# Rapide64a.net
KiCad netlist of a schematic drawn in EAGLE
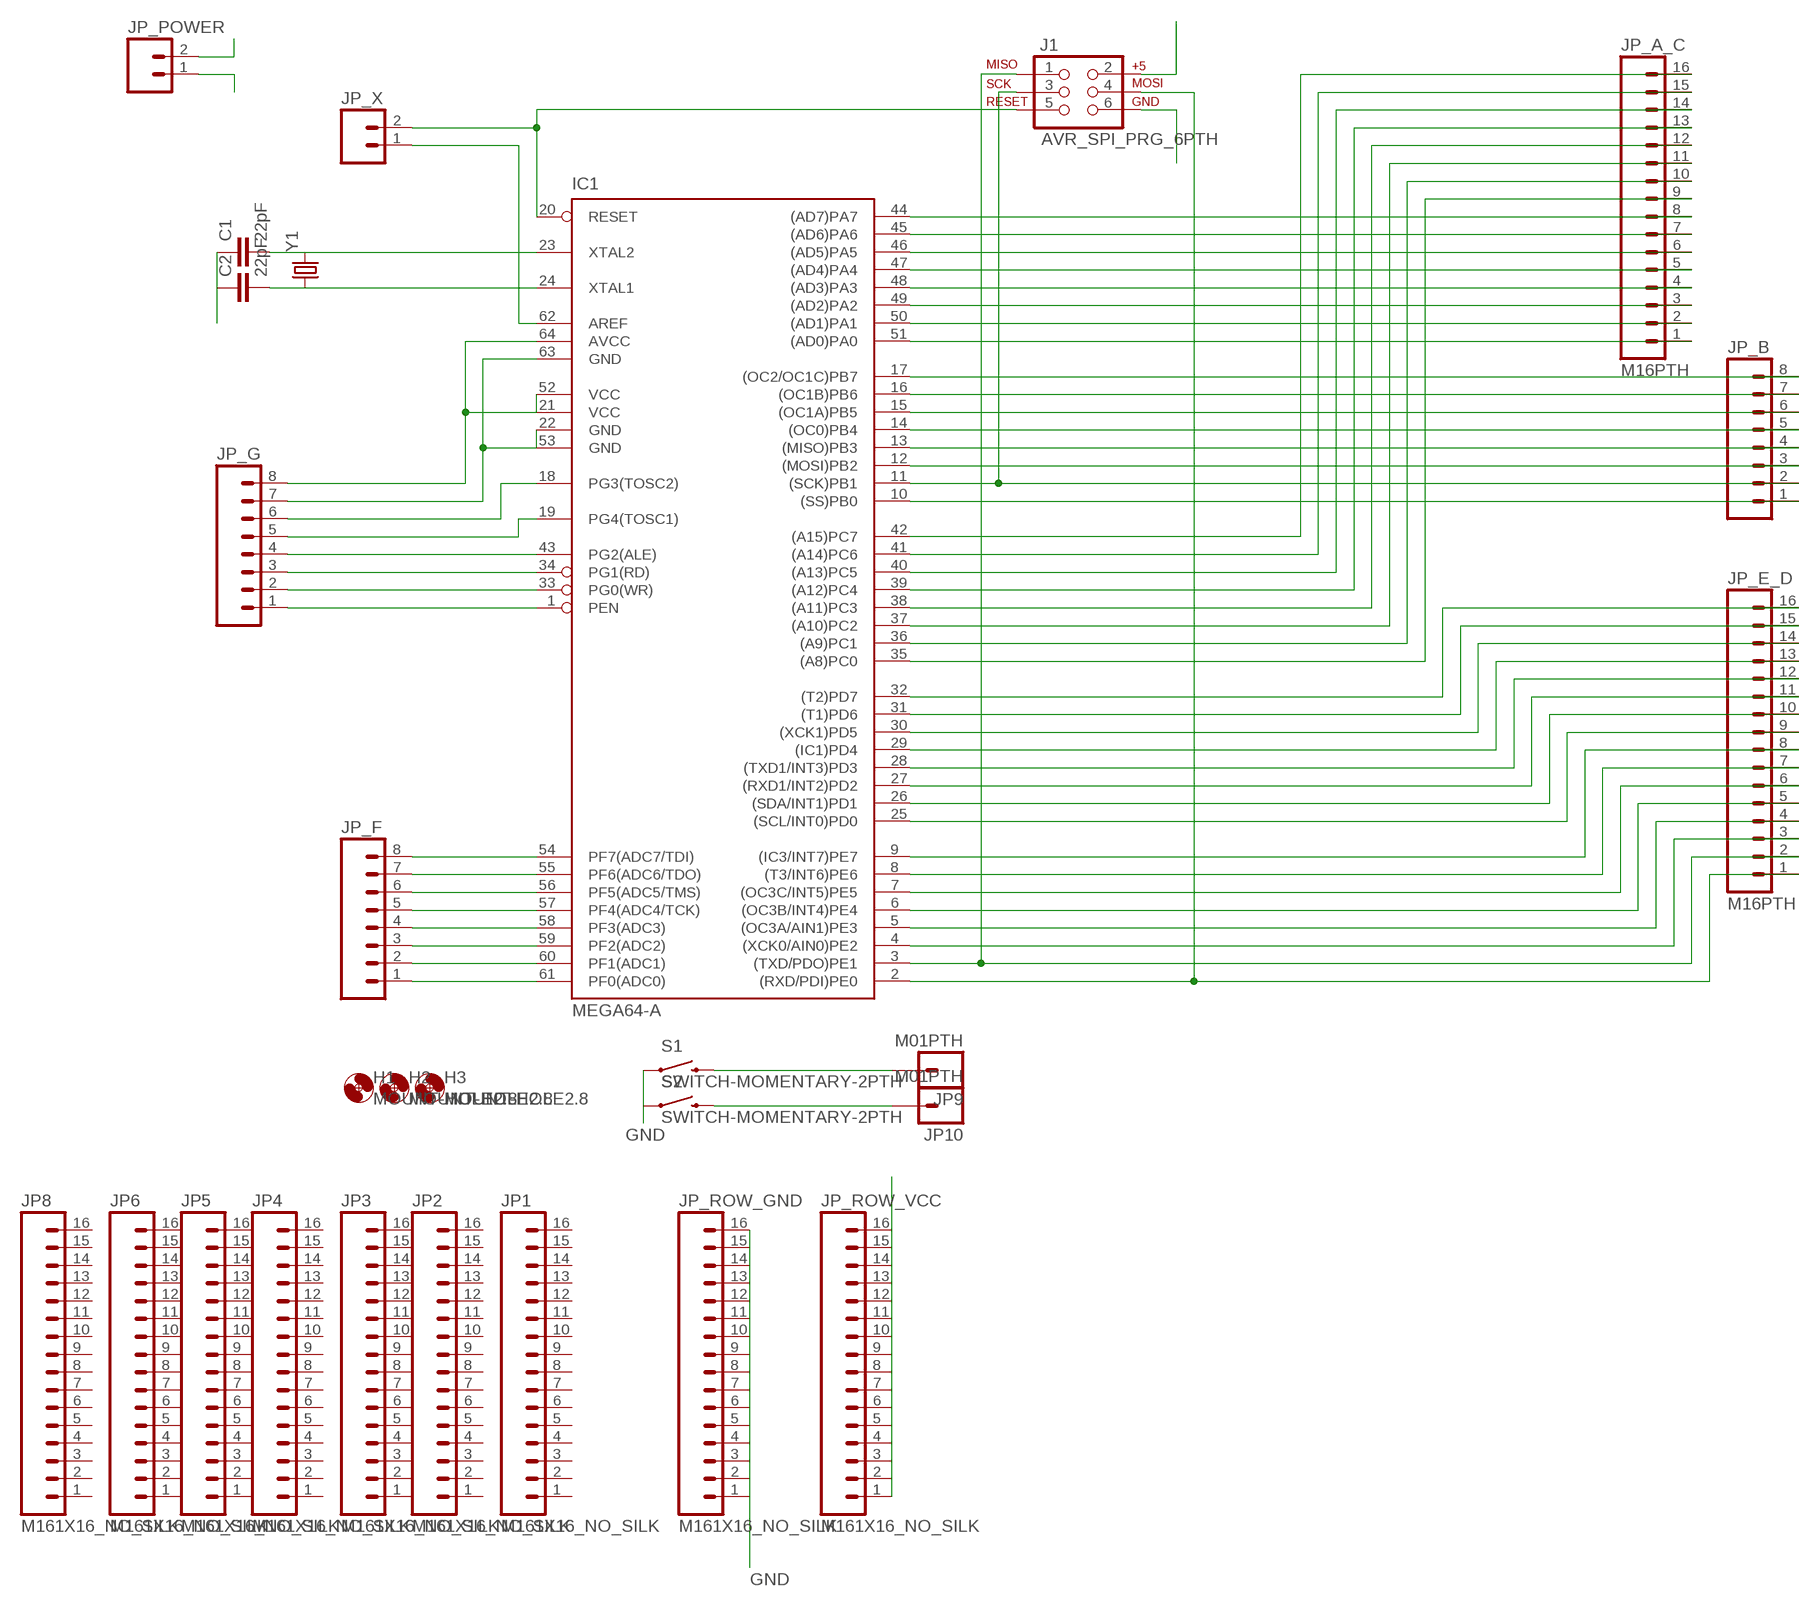
[diagram p0: schematic, sheet 1]

(export (version "E")
  (design (tool "Eeschema 10.0.6"))
  (components
    (comp (ref "C1")
      (value "22pF")
      (footprint "eagle-import:C025-024X044")
      (libsource (lib "eagle-import") (part "C-EU025-024X044"))
    )
    (comp (ref "C2")
      (value "22pF")
      (footprint "eagle-import:C025-024X044")
      (libsource (lib "eagle-import") (part "C-EU025-024X044"))
    )
    (comp (ref "H1")
      (value "MOUNT-HOLE2.8")
      (footprint "eagle-import:2,8")
      (libsource (lib "eagle-import") (part "MOUNT-HOLE2.8"))
    )
    (comp (ref "H2")
      (value "MOUNT-HOLE2.8")
      (footprint "eagle-import:2,8")
      (libsource (lib "eagle-import") (part "MOUNT-HOLE2.8"))
    )
    (comp (ref "H3")
      (value "MOUNT-HOLE2.8")
      (footprint "eagle-import:2,8")
      (libsource (lib "eagle-import") (part "MOUNT-HOLE2.8"))
    )
    (comp (ref "IC1")
      (value "MEGA64-A")
      (footprint "eagle-import:TQFP64")
      (fields (field (name "MPN") "ATMEGA64-16AU"))
      (libsource (lib "eagle-import") (part "MEGA64-A"))
    )
    (comp (ref "J1")
      (value "AVR_SPI_PRG_6PTH")
      (footprint "eagle-import:2X3")
      (libsource (lib "eagle-import") (part "AVR_SPI_PRG_6PTH"))
    )
    (comp (ref "JP1")
      (value "M161X16_NO_SILK")
      (footprint "eagle-import:1X16_NO_SILK")
      (libsource (lib "eagle-import") (part "M161X16_NO_SILK"))
    )
    (comp (ref "JP2")
      (value "M161X16_NO_SILK")
      (footprint "eagle-import:1X16_NO_SILK")
      (libsource (lib "eagle-import") (part "M161X16_NO_SILK"))
    )
    (comp (ref "JP3")
      (value "M161X16_NO_SILK")
      (footprint "eagle-import:1X16_NO_SILK")
      (libsource (lib "eagle-import") (part "M161X16_NO_SILK"))
    )
    (comp (ref "JP4")
      (value "M161X16_NO_SILK")
      (footprint "eagle-import:1X16_NO_SILK")
      (libsource (lib "eagle-import") (part "M161X16_NO_SILK"))
    )
    (comp (ref "JP5")
      (value "M161X16_NO_SILK")
      (footprint "eagle-import:1X16_NO_SILK")
      (libsource (lib "eagle-import") (part "M161X16_NO_SILK"))
    )
    (comp (ref "JP6")
      (value "M161X16_NO_SILK")
      (footprint "eagle-import:1X16_NO_SILK")
      (libsource (lib "eagle-import") (part "M161X16_NO_SILK"))
    )
    (comp (ref "JP8")
      (value "M161X16_NO_SILK")
      (footprint "eagle-import:1X16_NO_SILK")
      (libsource (lib "eagle-import") (part "M161X16_NO_SILK"))
    )
    (comp (ref "JP9")
      (value "M01PTH")
      (footprint "eagle-import:1X01")
      (libsource (lib "eagle-import") (part "M01PTH"))
    )
    (comp (ref "JP10")
      (value "M01PTH")
      (footprint "eagle-import:1X01")
      (libsource (lib "eagle-import") (part "M01PTH"))
    )
    (comp (ref "JP_A_C")
      (value "M16PTH")
      (footprint "eagle-import:1X16")
      (libsource (lib "eagle-import") (part "M16PTH"))
    )
    (comp (ref "JP_B")
      (value "M081X08")
      (footprint "eagle-import:1X08")
      (libsource (lib "eagle-import") (part "M081X08"))
    )
    (comp (ref "JP_E_D")
      (value "M16PTH")
      (footprint "eagle-import:1X16")
      (libsource (lib "eagle-import") (part "M16PTH"))
    )
    (comp (ref "JP_F")
      (value "M081X08")
      (footprint "eagle-import:1X08")
      (libsource (lib "eagle-import") (part "M081X08"))
    )
    (comp (ref "JP_G")
      (value "M081X08")
      (footprint "eagle-import:1X08")
      (libsource (lib "eagle-import") (part "M081X08"))
    )
    (comp (ref "JP_POWER")
      (value "M02PTH")
      (footprint "eagle-import:1X02")
      (libsource (lib "eagle-import") (part "M02PTH"))
    )
    (comp (ref "JP_ROW_GND")
      (value "M161X16_NO_SILK")
      (footprint "eagle-import:1X16_NO_SILK")
      (libsource (lib "eagle-import") (part "M161X16_NO_SILK"))
    )
    (comp (ref "JP_ROW_VCC")
      (value "M161X16_NO_SILK")
      (footprint "eagle-import:1X16_NO_SILK")
      (libsource (lib "eagle-import") (part "M161X16_NO_SILK"))
    )
    (comp (ref "JP_X")
      (value "M02PTH")
      (footprint "eagle-import:1X02")
      (libsource (lib "eagle-import") (part "M02PTH"))
    )
    (comp (ref "S1")
      (value "SWITCH-MOMENTARY-2PTH")
      (footprint "eagle-import:TACTILE-PTH")
      (libsource (lib "eagle-import") (part "SWITCH-MOMENTARY-2PTH"))
    )
    (comp (ref "S2")
      (value "SWITCH-MOMENTARY-2PTH")
      (footprint "eagle-import:TACTILE-PTH")
      (libsource (lib "eagle-import") (part "SWITCH-MOMENTARY-2PTH"))
    )
    (comp (ref "Y1")
      (value "CRYSTALHC49UV")
      (footprint "eagle-import:HC49U-V")
      (libsource (lib "eagle-import") (part "CRYSTALHC49UV"))
    )
  )
  (nets
    (net (code "1") (name "/GND") (class "Default")
      (node (ref "C1") (pin "1") (pinfunction "1_1") (pintype "passive"))
      (node (ref "C2") (pin "1") (pinfunction "1_1") (pintype "passive"))
      (node (ref "IC1") (pin "22") (pinfunction "GND_22") (pintype "power_in"))
      (node (ref "IC1") (pin "53") (pinfunction "GND_53") (pintype "power_in"))
      (node (ref "IC1") (pin "63") (pinfunction "GND_63") (pintype "power_in"))
      (node (ref "J1") (pin "6") (pinfunction "6_6") (pintype "passive"))
      (node (ref "JP_G") (pin "7") (pinfunction "7_7") (pintype "passive"))
      (node (ref "JP_POWER") (pin "1") (pinfunction "1_1") (pintype "passive"))
      (node (ref "JP_ROW_GND") (pin "1") (pinfunction "1_1") (pintype "passive"))
      (node (ref "JP_ROW_GND") (pin "10") (pinfunction "10_10") (pintype "passive"))
      (node (ref "JP_ROW_GND") (pin "11") (pinfunction "11_11") (pintype "passive"))
      (node (ref "JP_ROW_GND") (pin "12") (pinfunction "12_12") (pintype "passive"))
      (node (ref "JP_ROW_GND") (pin "13") (pinfunction "13_13") (pintype "passive"))
      (node (ref "JP_ROW_GND") (pin "14") (pinfunction "14_14") (pintype "passive"))
      (node (ref "JP_ROW_GND") (pin "15") (pinfunction "15_15") (pintype "passive"))
      (node (ref "JP_ROW_GND") (pin "16") (pinfunction "16_16") (pintype "passive"))
      (node (ref "JP_ROW_GND") (pin "2") (pinfunction "2_2") (pintype "passive"))
      (node (ref "JP_ROW_GND") (pin "3") (pinfunction "3_3") (pintype "passive"))
      (node (ref "JP_ROW_GND") (pin "4") (pinfunction "4_4") (pintype "passive"))
      (node (ref "JP_ROW_GND") (pin "5") (pinfunction "5_5") (pintype "passive"))
      (node (ref "JP_ROW_GND") (pin "6") (pinfunction "6_6") (pintype "passive"))
      (node (ref "JP_ROW_GND") (pin "7") (pinfunction "7_7") (pintype "passive"))
      (node (ref "JP_ROW_GND") (pin "8") (pinfunction "8_8") (pintype "passive"))
      (node (ref "JP_ROW_GND") (pin "9") (pinfunction "9_9") (pintype "passive"))
      (node (ref "S1") (pin "1") (pinfunction "1_1") (pintype "passive"))
      (node (ref "S2") (pin "1") (pinfunction "1_1") (pintype "passive"))
    )
    (net (code "2") (name "/VCC") (class "Default")
      (node (ref "IC1") (pin "21") (pinfunction "VCC_21") (pintype "power_in"))
      (node (ref "IC1") (pin "52") (pinfunction "VCC_52") (pintype "power_in"))
      (node (ref "IC1") (pin "64") (pinfunction "AVCC_64") (pintype "power_in"))
      (node (ref "J1") (pin "2") (pinfunction "2_2") (pintype "passive"))
      (node (ref "JP_G") (pin "8") (pinfunction "8_8") (pintype "passive"))
      (node (ref "JP_POWER") (pin "2") (pinfunction "2_2") (pintype "passive"))
      (node (ref "JP_ROW_VCC") (pin "1") (pinfunction "1_1") (pintype "passive"))
      (node (ref "JP_ROW_VCC") (pin "10") (pinfunction "10_10") (pintype "passive"))
      (node (ref "JP_ROW_VCC") (pin "11") (pinfunction "11_11") (pintype "passive"))
      (node (ref "JP_ROW_VCC") (pin "12") (pinfunction "12_12") (pintype "passive"))
      (node (ref "JP_ROW_VCC") (pin "13") (pinfunction "13_13") (pintype "passive"))
      (node (ref "JP_ROW_VCC") (pin "14") (pinfunction "14_14") (pintype "passive"))
      (node (ref "JP_ROW_VCC") (pin "15") (pinfunction "15_15") (pintype "passive"))
      (node (ref "JP_ROW_VCC") (pin "16") (pinfunction "16_16") (pintype "passive"))
      (node (ref "JP_ROW_VCC") (pin "2") (pinfunction "2_2") (pintype "passive"))
      (node (ref "JP_ROW_VCC") (pin "3") (pinfunction "3_3") (pintype "passive"))
      (node (ref "JP_ROW_VCC") (pin "4") (pinfunction "4_4") (pintype "passive"))
      (node (ref "JP_ROW_VCC") (pin "5") (pinfunction "5_5") (pintype "passive"))
      (node (ref "JP_ROW_VCC") (pin "6") (pinfunction "6_6") (pintype "passive"))
      (node (ref "JP_ROW_VCC") (pin "7") (pinfunction "7_7") (pintype "passive"))
      (node (ref "JP_ROW_VCC") (pin "8") (pinfunction "8_8") (pintype "passive"))
      (node (ref "JP_ROW_VCC") (pin "9") (pinfunction "9_9") (pintype "passive"))
    )
    (net (code "3") (name "Net-(IC1-(A8)PC0)") (class "Default")
      (node (ref "IC1") (pin "35") (pinfunction "(A8)PC0_35") (pintype "output"))
      (node (ref "JP_A_C") (pin "9") (pinfunction "9_9") (pintype "passive"))
    )
    (net (code "4") (name "Net-(IC1-(A9)PC1)") (class "Default")
      (node (ref "IC1") (pin "36") (pinfunction "(A9)PC1_36") (pintype "output"))
      (node (ref "JP_A_C") (pin "10") (pinfunction "10_10") (pintype "passive"))
    )
    (net (code "5") (name "Net-(IC1-(A10)PC2)") (class "Default")
      (node (ref "IC1") (pin "37") (pinfunction "(A10)PC2_37") (pintype "output"))
      (node (ref "JP_A_C") (pin "11") (pinfunction "11_11") (pintype "passive"))
    )
    (net (code "6") (name "Net-(IC1-(A11)PC3)") (class "Default")
      (node (ref "IC1") (pin "38") (pinfunction "(A11)PC3_38") (pintype "output"))
      (node (ref "JP_A_C") (pin "12") (pinfunction "12_12") (pintype "passive"))
    )
    (net (code "7") (name "Net-(IC1-(A12)PC4)") (class "Default")
      (node (ref "IC1") (pin "39") (pinfunction "(A12)PC4_39") (pintype "output"))
      (node (ref "JP_A_C") (pin "13") (pinfunction "13_13") (pintype "passive"))
    )
    (net (code "8") (name "Net-(IC1-(A13)PC5)") (class "Default")
      (node (ref "IC1") (pin "40") (pinfunction "(A13)PC5_40") (pintype "output"))
      (node (ref "JP_A_C") (pin "14") (pinfunction "14_14") (pintype "passive"))
    )
    (net (code "9") (name "Net-(IC1-(A14)PC6)") (class "Default")
      (node (ref "IC1") (pin "41") (pinfunction "(A14)PC6_41") (pintype "output"))
      (node (ref "JP_A_C") (pin "15") (pinfunction "15_15") (pintype "passive"))
    )
    (net (code "10") (name "Net-(IC1-(A15)PC7)") (class "Default")
      (node (ref "IC1") (pin "42") (pinfunction "(A15)PC7_42") (pintype "output"))
      (node (ref "JP_A_C") (pin "16") (pinfunction "16_16") (pintype "passive"))
    )
    (net (code "11") (name "Net-(IC1-(AD0)PA0)") (class "Default")
      (node (ref "IC1") (pin "51") (pinfunction "(AD0)PA0_51") (pintype "bidirectional"))
      (node (ref "JP_A_C") (pin "1") (pinfunction "1_1") (pintype "passive"))
    )
    (net (code "12") (name "Net-(IC1-(AD1)PA1)") (class "Default")
      (node (ref "IC1") (pin "50") (pinfunction "(AD1)PA1_50") (pintype "bidirectional"))
      (node (ref "JP_A_C") (pin "2") (pinfunction "2_2") (pintype "passive"))
    )
    (net (code "13") (name "Net-(IC1-(AD2)PA2)") (class "Default")
      (node (ref "IC1") (pin "49") (pinfunction "(AD2)PA2_49") (pintype "bidirectional"))
      (node (ref "JP_A_C") (pin "3") (pinfunction "3_3") (pintype "passive"))
    )
    (net (code "14") (name "Net-(IC1-(AD3)PA3)") (class "Default")
      (node (ref "IC1") (pin "48") (pinfunction "(AD3)PA3_48") (pintype "bidirectional"))
      (node (ref "JP_A_C") (pin "4") (pinfunction "4_4") (pintype "passive"))
    )
    (net (code "15") (name "Net-(IC1-(AD4)PA4)") (class "Default")
      (node (ref "IC1") (pin "47") (pinfunction "(AD4)PA4_47") (pintype "bidirectional"))
      (node (ref "JP_A_C") (pin "5") (pinfunction "5_5") (pintype "passive"))
    )
    (net (code "16") (name "Net-(IC1-(AD5)PA5)") (class "Default")
      (node (ref "IC1") (pin "46") (pinfunction "(AD5)PA5_46") (pintype "bidirectional"))
      (node (ref "JP_A_C") (pin "6") (pinfunction "6_6") (pintype "passive"))
    )
    (net (code "17") (name "Net-(IC1-(AD6)PA6)") (class "Default")
      (node (ref "IC1") (pin "45") (pinfunction "(AD6)PA6_45") (pintype "bidirectional"))
      (node (ref "JP_A_C") (pin "7") (pinfunction "7_7") (pintype "passive"))
    )
    (net (code "18") (name "Net-(IC1-(AD7)PA7)") (class "Default")
      (node (ref "IC1") (pin "44") (pinfunction "(AD7)PA7_44") (pintype "bidirectional"))
      (node (ref "JP_A_C") (pin "8") (pinfunction "8_8") (pintype "passive"))
    )
    (net (code "19") (name "Net-(IC1-(IC1)PD4)") (class "Default")
      (node (ref "IC1") (pin "29") (pinfunction "(IC1)PD4_29") (pintype "bidirectional"))
      (node (ref "JP_E_D") (pin "13") (pinfunction "13_13") (pintype "passive"))
    )
    (net (code "20") (name "Net-(IC1-(IC3{slash}INT7)PE7)") (class "Default")
      (node (ref "IC1") (pin "9") (pinfunction "(IC3/INT7)PE7_9") (pintype "bidirectional"))
      (node (ref "JP_E_D") (pin "8") (pinfunction "8_8") (pintype "passive"))
    )
    (net (code "21") (name "Net-(IC1-(MISO)PB3)") (class "Default")
      (node (ref "IC1") (pin "13") (pinfunction "(MISO)PB3_13") (pintype "bidirectional"))
      (node (ref "JP_B") (pin "4") (pinfunction "4_4") (pintype "passive"))
    )
    (net (code "22") (name "Net-(IC1-(MOSI)PB2)") (class "Default")
      (node (ref "IC1") (pin "12") (pinfunction "(MOSI)PB2_12") (pintype "bidirectional"))
      (node (ref "JP_B") (pin "3") (pinfunction "3_3") (pintype "passive"))
    )
    (net (code "23") (name "Net-(IC1-(OC0)PB4)") (class "Default")
      (node (ref "IC1") (pin "14") (pinfunction "(OC0)PB4_14") (pintype "bidirectional"))
      (node (ref "JP_B") (pin "5") (pinfunction "5_5") (pintype "passive"))
    )
    (net (code "24") (name "Net-(IC1-(OC1A)PB5)") (class "Default")
      (node (ref "IC1") (pin "15") (pinfunction "(OC1A)PB5_15") (pintype "bidirectional"))
      (node (ref "JP_B") (pin "6") (pinfunction "6_6") (pintype "passive"))
    )
    (net (code "25") (name "Net-(IC1-(OC1B)PB6)") (class "Default")
      (node (ref "IC1") (pin "16") (pinfunction "(OC1B)PB6_16") (pintype "bidirectional"))
      (node (ref "JP_B") (pin "7") (pinfunction "7_7") (pintype "passive"))
    )
    (net (code "26") (name "Net-(IC1-(OC2{slash}OC1C)PB7)") (class "Default")
      (node (ref "IC1") (pin "17") (pinfunction "(OC2/OC1C)PB7_17") (pintype "bidirectional"))
      (node (ref "JP_B") (pin "8") (pinfunction "8_8") (pintype "passive"))
    )
    (net (code "27") (name "Net-(IC1-(OC3A{slash}AIN1)PE3)") (class "Default")
      (node (ref "IC1") (pin "5") (pinfunction "(OC3A/AIN1)PE3_5") (pintype "bidirectional"))
      (node (ref "JP_E_D") (pin "4") (pinfunction "4_4") (pintype "passive"))
    )
    (net (code "28") (name "Net-(IC1-(OC3B{slash}INT4)PE4)") (class "Default")
      (node (ref "IC1") (pin "6") (pinfunction "(OC3B/INT4)PE4_6") (pintype "bidirectional"))
      (node (ref "JP_E_D") (pin "5") (pinfunction "5_5") (pintype "passive"))
    )
    (net (code "29") (name "Net-(IC1-(OC3C{slash}INT5)PE5)") (class "Default")
      (node (ref "IC1") (pin "7") (pinfunction "(OC3C/INT5)PE5_7") (pintype "bidirectional"))
      (node (ref "JP_E_D") (pin "6") (pinfunction "6_6") (pintype "passive"))
    )
    (net (code "30") (name "Net-(IC1-(RXD1{slash}INT2)PD2)") (class "Default")
      (node (ref "IC1") (pin "27") (pinfunction "(RXD1/INT2)PD2_27") (pintype "bidirectional"))
      (node (ref "JP_E_D") (pin "11") (pinfunction "11_11") (pintype "passive"))
    )
    (net (code "31") (name "Net-(IC1-(RXD{slash}PDI)PE0)") (class "Default")
      (node (ref "IC1") (pin "2") (pinfunction "(RXD/PDI)PE0_2") (pintype "bidirectional"))
      (node (ref "J1") (pin "4") (pinfunction "4_4") (pintype "passive"))
      (node (ref "JP_E_D") (pin "1") (pinfunction "1_1") (pintype "passive"))
    )
    (net (code "32") (name "Net-(IC1-(SCK)PB1)") (class "Default")
      (node (ref "IC1") (pin "11") (pinfunction "(SCK)PB1_11") (pintype "bidirectional"))
      (node (ref "J1") (pin "3") (pinfunction "3_3") (pintype "passive"))
      (node (ref "JP_B") (pin "2") (pinfunction "2_2") (pintype "passive"))
    )
    (net (code "33") (name "Net-(IC1-(SCL{slash}INT0)PD0)") (class "Default")
      (node (ref "IC1") (pin "25") (pinfunction "(SCL/INT0)PD0_25") (pintype "bidirectional"))
      (node (ref "JP_E_D") (pin "9") (pinfunction "9_9") (pintype "passive"))
    )
    (net (code "34") (name "Net-(IC1-(SDA{slash}INT1)PD1)") (class "Default")
      (node (ref "IC1") (pin "26") (pinfunction "(SDA/INT1)PD1_26") (pintype "bidirectional"))
      (node (ref "JP_E_D") (pin "10") (pinfunction "10_10") (pintype "passive"))
    )
    (net (code "35") (name "Net-(IC1-(SS)PB0)") (class "Default")
      (node (ref "IC1") (pin "10") (pinfunction "(SS)PB0_10") (pintype "bidirectional"))
      (node (ref "JP_B") (pin "1") (pinfunction "1_1") (pintype "passive"))
    )
    (net (code "36") (name "Net-(IC1-(T1)PD6)") (class "Default")
      (node (ref "IC1") (pin "31") (pinfunction "(T1)PD6_31") (pintype "bidirectional"))
      (node (ref "JP_E_D") (pin "15") (pinfunction "15_15") (pintype "passive"))
    )
    (net (code "37") (name "Net-(IC1-(T2)PD7)") (class "Default")
      (node (ref "IC1") (pin "32") (pinfunction "(T2)PD7_32") (pintype "bidirectional"))
      (node (ref "JP_E_D") (pin "16") (pinfunction "16_16") (pintype "passive"))
    )
    (net (code "38") (name "Net-(IC1-(T3{slash}INT6)PE6)") (class "Default")
      (node (ref "IC1") (pin "8") (pinfunction "(T3/INT6)PE6_8") (pintype "bidirectional"))
      (node (ref "JP_E_D") (pin "7") (pinfunction "7_7") (pintype "passive"))
    )
    (net (code "39") (name "Net-(IC1-(TXD1{slash}INT3)PD3)") (class "Default")
      (node (ref "IC1") (pin "28") (pinfunction "(TXD1/INT3)PD3_28") (pintype "bidirectional"))
      (node (ref "JP_E_D") (pin "12") (pinfunction "12_12") (pintype "passive"))
    )
    (net (code "40") (name "Net-(IC1-(TXD{slash}PDO)PE1)") (class "Default")
      (node (ref "IC1") (pin "3") (pinfunction "(TXD/PDO)PE1_3") (pintype "bidirectional"))
      (node (ref "J1") (pin "1") (pinfunction "1_1") (pintype "passive"))
      (node (ref "JP_E_D") (pin "2") (pinfunction "2_2") (pintype "passive"))
    )
    (net (code "41") (name "Net-(IC1-(XCK0{slash}AIN0)PE2)") (class "Default")
      (node (ref "IC1") (pin "4") (pinfunction "(XCK0/AIN0)PE2_4") (pintype "bidirectional"))
      (node (ref "JP_E_D") (pin "3") (pinfunction "3_3") (pintype "passive"))
    )
    (net (code "42") (name "Net-(IC1-(XCK1)PD5)") (class "Default")
      (node (ref "IC1") (pin "30") (pinfunction "(XCK1)PD5_30") (pintype "bidirectional"))
      (node (ref "JP_E_D") (pin "14") (pinfunction "14_14") (pintype "passive"))
    )
    (net (code "43") (name "Net-(IC1-AREF)") (class "Default")
      (node (ref "IC1") (pin "62") (pinfunction "AREF_62") (pintype "passive"))
      (node (ref "JP_X") (pin "1") (pinfunction "1_1") (pintype "passive"))
    )
    (net (code "44") (name "Net-(IC1-PEN)") (class "Default")
      (node (ref "IC1") (pin "1") (pinfunction "PEN_1") (pintype "input"))
      (node (ref "JP_G") (pin "1") (pinfunction "1_1") (pintype "passive"))
    )
    (net (code "45") (name "Net-(IC1-PF0(ADC0))") (class "Default")
      (node (ref "IC1") (pin "61") (pinfunction "PF0(ADC0)_61") (pintype "input"))
      (node (ref "JP_F") (pin "1") (pinfunction "1_1") (pintype "passive"))
    )
    (net (code "46") (name "Net-(IC1-PF1(ADC1))") (class "Default")
      (node (ref "IC1") (pin "60") (pinfunction "PF1(ADC1)_60") (pintype "input"))
      (node (ref "JP_F") (pin "2") (pinfunction "2_2") (pintype "passive"))
    )
    (net (code "47") (name "Net-(IC1-PF2(ADC2))") (class "Default")
      (node (ref "IC1") (pin "59") (pinfunction "PF2(ADC2)_59") (pintype "input"))
      (node (ref "JP_F") (pin "3") (pinfunction "3_3") (pintype "passive"))
    )
    (net (code "48") (name "Net-(IC1-PF3(ADC3))") (class "Default")
      (node (ref "IC1") (pin "58") (pinfunction "PF3(ADC3)_58") (pintype "input"))
      (node (ref "JP_F") (pin "4") (pinfunction "4_4") (pintype "passive"))
    )
    (net (code "49") (name "Net-(IC1-PF4(ADC4{slash}TCK))") (class "Default")
      (node (ref "IC1") (pin "57") (pinfunction "PF4(ADC4/TCK)_57") (pintype "input"))
      (node (ref "JP_F") (pin "5") (pinfunction "5_5") (pintype "passive"))
    )
    (net (code "50") (name "Net-(IC1-PF5(ADC5{slash}TMS))") (class "Default")
      (node (ref "IC1") (pin "56") (pinfunction "PF5(ADC5/TMS)_56") (pintype "input"))
      (node (ref "JP_F") (pin "6") (pinfunction "6_6") (pintype "passive"))
    )
    (net (code "51") (name "Net-(IC1-PF6(ADC6{slash}TDO))") (class "Default")
      (node (ref "IC1") (pin "55") (pinfunction "PF6(ADC6/TDO)_55") (pintype "input"))
      (node (ref "JP_F") (pin "7") (pinfunction "7_7") (pintype "passive"))
    )
    (net (code "52") (name "Net-(IC1-PF7(ADC7{slash}TDI))") (class "Default")
      (node (ref "IC1") (pin "54") (pinfunction "PF7(ADC7/TDI)_54") (pintype "input"))
      (node (ref "JP_F") (pin "8") (pinfunction "8_8") (pintype "passive"))
    )
    (net (code "53") (name "Net-(IC1-PG0(WR))") (class "Default")
      (node (ref "IC1") (pin "33") (pinfunction "PG0(WR)_33") (pintype "bidirectional"))
      (node (ref "JP_G") (pin "2") (pinfunction "2_2") (pintype "passive"))
    )
    (net (code "54") (name "Net-(IC1-PG1(RD))") (class "Default")
      (node (ref "IC1") (pin "34") (pinfunction "PG1(RD)_34") (pintype "bidirectional"))
      (node (ref "JP_G") (pin "3") (pinfunction "3_3") (pintype "passive"))
    )
    (net (code "55") (name "Net-(IC1-PG2(ALE))") (class "Default")
      (node (ref "IC1") (pin "43") (pinfunction "PG2(ALE)_43") (pintype "bidirectional"))
      (node (ref "JP_G") (pin "4") (pinfunction "4_4") (pintype "passive"))
    )
    (net (code "56") (name "Net-(IC1-PG3(TOSC2))") (class "Default")
      (node (ref "IC1") (pin "18") (pinfunction "PG3(TOSC2)_18") (pintype "bidirectional"))
      (node (ref "JP_G") (pin "6") (pinfunction "6_6") (pintype "passive"))
    )
    (net (code "57") (name "Net-(IC1-PG4(TOSC1))") (class "Default")
      (node (ref "IC1") (pin "19") (pinfunction "PG4(TOSC1)_19") (pintype "bidirectional"))
      (node (ref "JP_G") (pin "5") (pinfunction "5_5") (pintype "passive"))
    )
    (net (code "58") (name "Net-(IC1-RESET)") (class "Default")
      (node (ref "IC1") (pin "20") (pinfunction "RESET_20") (pintype "input"))
      (node (ref "J1") (pin "5") (pinfunction "5_5") (pintype "passive"))
      (node (ref "JP_X") (pin "2") (pinfunction "2_2") (pintype "passive"))
    )
    (net (code "59") (name "Net-(IC1-XTAL1)") (class "Default")
      (node (ref "C2") (pin "2") (pinfunction "2_2") (pintype "passive"))
      (node (ref "IC1") (pin "24") (pinfunction "XTAL1_24") (pintype "bidirectional"))
      (node (ref "Y1") (pin "1") (pinfunction "1_1") (pintype "passive"))
    )
    (net (code "60") (name "Net-(IC1-XTAL2)") (class "Default")
      (node (ref "C1") (pin "2") (pinfunction "2_2") (pintype "passive"))
      (node (ref "IC1") (pin "23") (pinfunction "XTAL2_23") (pintype "bidirectional"))
      (node (ref "Y1") (pin "2") (pinfunction "2_2") (pintype "passive"))
    )
    (net (code "61") (name "Net-(S1-2)") (class "Default")
      (node (ref "JP9") (pin "1") (pinfunction "1_1") (pintype "passive"))
      (node (ref "S1") (pin "3") (pinfunction "2_3") (pintype "passive"))
    )
    (net (code "62") (name "Net-(S2-2)") (class "Default")
      (node (ref "JP10") (pin "1") (pinfunction "1_1") (pintype "passive"))
      (node (ref "S2") (pin "3") (pinfunction "2_3") (pintype "passive"))
    )
    (net (code "63") (name "unconnected-(JP1-Pad1)") (class "Default")
      (node (ref "JP1") (pin "1") (pinfunction "1_1") (pintype "passive"))
    )
    (net (code "64") (name "unconnected-(JP1-Pad2)") (class "Default")
      (node (ref "JP1") (pin "2") (pinfunction "2_2") (pintype "passive"))
    )
    (net (code "65") (name "unconnected-(JP1-Pad3)") (class "Default")
      (node (ref "JP1") (pin "3") (pinfunction "3_3") (pintype "passive"))
    )
    (net (code "66") (name "unconnected-(JP1-Pad4)") (class "Default")
      (node (ref "JP1") (pin "4") (pinfunction "4_4") (pintype "passive"))
    )
    (net (code "67") (name "unconnected-(JP1-Pad5)") (class "Default")
      (node (ref "JP1") (pin "5") (pinfunction "5_5") (pintype "passive"))
    )
    (net (code "68") (name "unconnected-(JP1-Pad6)") (class "Default")
      (node (ref "JP1") (pin "6") (pinfunction "6_6") (pintype "passive"))
    )
    (net (code "69") (name "unconnected-(JP1-Pad7)") (class "Default")
      (node (ref "JP1") (pin "7") (pinfunction "7_7") (pintype "passive"))
    )
    (net (code "70") (name "unconnected-(JP1-Pad8)") (class "Default")
      (node (ref "JP1") (pin "8") (pinfunction "8_8") (pintype "passive"))
    )
    (net (code "71") (name "unconnected-(JP1-Pad9)") (class "Default")
      (node (ref "JP1") (pin "9") (pinfunction "9_9") (pintype "passive"))
    )
    (net (code "72") (name "unconnected-(JP1-Pad10)") (class "Default")
      (node (ref "JP1") (pin "10") (pinfunction "10_10") (pintype "passive"))
    )
    (net (code "73") (name "unconnected-(JP1-Pad11)") (class "Default")
      (node (ref "JP1") (pin "11") (pinfunction "11_11") (pintype "passive"))
    )
    (net (code "74") (name "unconnected-(JP1-Pad12)") (class "Default")
      (node (ref "JP1") (pin "12") (pinfunction "12_12") (pintype "passive"))
    )
    (net (code "75") (name "unconnected-(JP1-Pad13)") (class "Default")
      (node (ref "JP1") (pin "13") (pinfunction "13_13") (pintype "passive"))
    )
    (net (code "76") (name "unconnected-(JP1-Pad14)") (class "Default")
      (node (ref "JP1") (pin "14") (pinfunction "14_14") (pintype "passive"))
    )
    (net (code "77") (name "unconnected-(JP1-Pad15)") (class "Default")
      (node (ref "JP1") (pin "15") (pinfunction "15_15") (pintype "passive"))
    )
    (net (code "78") (name "unconnected-(JP1-Pad16)") (class "Default")
      (node (ref "JP1") (pin "16") (pinfunction "16_16") (pintype "passive"))
    )
    (net (code "79") (name "unconnected-(JP2-Pad1)") (class "Default")
      (node (ref "JP2") (pin "1") (pinfunction "1_1") (pintype "passive"))
    )
    (net (code "80") (name "unconnected-(JP2-Pad2)") (class "Default")
      (node (ref "JP2") (pin "2") (pinfunction "2_2") (pintype "passive"))
    )
    (net (code "81") (name "unconnected-(JP2-Pad3)") (class "Default")
      (node (ref "JP2") (pin "3") (pinfunction "3_3") (pintype "passive"))
    )
    (net (code "82") (name "unconnected-(JP2-Pad4)") (class "Default")
      (node (ref "JP2") (pin "4") (pinfunction "4_4") (pintype "passive"))
    )
    (net (code "83") (name "unconnected-(JP2-Pad5)") (class "Default")
      (node (ref "JP2") (pin "5") (pinfunction "5_5") (pintype "passive"))
    )
    (net (code "84") (name "unconnected-(JP2-Pad6)") (class "Default")
      (node (ref "JP2") (pin "6") (pinfunction "6_6") (pintype "passive"))
    )
    (net (code "85") (name "unconnected-(JP2-Pad7)") (class "Default")
      (node (ref "JP2") (pin "7") (pinfunction "7_7") (pintype "passive"))
    )
    (net (code "86") (name "unconnected-(JP2-Pad8)") (class "Default")
      (node (ref "JP2") (pin "8") (pinfunction "8_8") (pintype "passive"))
    )
    (net (code "87") (name "unconnected-(JP2-Pad9)") (class "Default")
      (node (ref "JP2") (pin "9") (pinfunction "9_9") (pintype "passive"))
    )
    (net (code "88") (name "unconnected-(JP2-Pad10)") (class "Default")
      (node (ref "JP2") (pin "10") (pinfunction "10_10") (pintype "passive"))
    )
    (net (code "89") (name "unconnected-(JP2-Pad11)") (class "Default")
      (node (ref "JP2") (pin "11") (pinfunction "11_11") (pintype "passive"))
    )
    (net (code "90") (name "unconnected-(JP2-Pad12)") (class "Default")
      (node (ref "JP2") (pin "12") (pinfunction "12_12") (pintype "passive"))
    )
    (net (code "91") (name "unconnected-(JP2-Pad13)") (class "Default")
      (node (ref "JP2") (pin "13") (pinfunction "13_13") (pintype "passive"))
    )
    (net (code "92") (name "unconnected-(JP2-Pad14)") (class "Default")
      (node (ref "JP2") (pin "14") (pinfunction "14_14") (pintype "passive"))
    )
    (net (code "93") (name "unconnected-(JP2-Pad15)") (class "Default")
      (node (ref "JP2") (pin "15") (pinfunction "15_15") (pintype "passive"))
    )
    (net (code "94") (name "unconnected-(JP2-Pad16)") (class "Default")
      (node (ref "JP2") (pin "16") (pinfunction "16_16") (pintype "passive"))
    )
    (net (code "95") (name "unconnected-(JP3-Pad1)") (class "Default")
      (node (ref "JP3") (pin "1") (pinfunction "1_1") (pintype "passive"))
    )
    (net (code "96") (name "unconnected-(JP3-Pad2)") (class "Default")
      (node (ref "JP3") (pin "2") (pinfunction "2_2") (pintype "passive"))
    )
    (net (code "97") (name "unconnected-(JP3-Pad3)") (class "Default")
      (node (ref "JP3") (pin "3") (pinfunction "3_3") (pintype "passive"))
    )
    (net (code "98") (name "unconnected-(JP3-Pad4)") (class "Default")
      (node (ref "JP3") (pin "4") (pinfunction "4_4") (pintype "passive"))
    )
    (net (code "99") (name "unconnected-(JP3-Pad5)") (class "Default")
      (node (ref "JP3") (pin "5") (pinfunction "5_5") (pintype "passive"))
    )
    (net (code "100") (name "unconnected-(JP3-Pad6)") (class "Default")
      (node (ref "JP3") (pin "6") (pinfunction "6_6") (pintype "passive"))
    )
    (net (code "101") (name "unconnected-(JP3-Pad7)") (class "Default")
      (node (ref "JP3") (pin "7") (pinfunction "7_7") (pintype "passive"))
    )
    (net (code "102") (name "unconnected-(JP3-Pad8)") (class "Default")
      (node (ref "JP3") (pin "8") (pinfunction "8_8") (pintype "passive"))
    )
    (net (code "103") (name "unconnected-(JP3-Pad9)") (class "Default")
      (node (ref "JP3") (pin "9") (pinfunction "9_9") (pintype "passive"))
    )
    (net (code "104") (name "unconnected-(JP3-Pad10)") (class "Default")
      (node (ref "JP3") (pin "10") (pinfunction "10_10") (pintype "passive"))
    )
    (net (code "105") (name "unconnected-(JP3-Pad11)") (class "Default")
      (node (ref "JP3") (pin "11") (pinfunction "11_11") (pintype "passive"))
    )
    (net (code "106") (name "unconnected-(JP3-Pad12)") (class "Default")
      (node (ref "JP3") (pin "12") (pinfunction "12_12") (pintype "passive"))
    )
    (net (code "107") (name "unconnected-(JP3-Pad13)") (class "Default")
      (node (ref "JP3") (pin "13") (pinfunction "13_13") (pintype "passive"))
    )
    (net (code "108") (name "unconnected-(JP3-Pad14)") (class "Default")
      (node (ref "JP3") (pin "14") (pinfunction "14_14") (pintype "passive"))
    )
    (net (code "109") (name "unconnected-(JP3-Pad15)") (class "Default")
      (node (ref "JP3") (pin "15") (pinfunction "15_15") (pintype "passive"))
    )
    (net (code "110") (name "unconnected-(JP3-Pad16)") (class "Default")
      (node (ref "JP3") (pin "16") (pinfunction "16_16") (pintype "passive"))
    )
    (net (code "111") (name "unconnected-(JP4-Pad1)") (class "Default")
      (node (ref "JP4") (pin "1") (pinfunction "1_1") (pintype "passive"))
    )
    (net (code "112") (name "unconnected-(JP4-Pad2)") (class "Default")
      (node (ref "JP4") (pin "2") (pinfunction "2_2") (pintype "passive"))
    )
    (net (code "113") (name "unconnected-(JP4-Pad3)") (class "Default")
      (node (ref "JP4") (pin "3") (pinfunction "3_3") (pintype "passive"))
    )
    (net (code "114") (name "unconnected-(JP4-Pad4)") (class "Default")
      (node (ref "JP4") (pin "4") (pinfunction "4_4") (pintype "passive"))
    )
    (net (code "115") (name "unconnected-(JP4-Pad5)") (class "Default")
      (node (ref "JP4") (pin "5") (pinfunction "5_5") (pintype "passive"))
    )
    (net (code "116") (name "unconnected-(JP4-Pad6)") (class "Default")
      (node (ref "JP4") (pin "6") (pinfunction "6_6") (pintype "passive"))
    )
    (net (code "117") (name "unconnected-(JP4-Pad7)") (class "Default")
      (node (ref "JP4") (pin "7") (pinfunction "7_7") (pintype "passive"))
    )
    (net (code "118") (name "unconnected-(JP4-Pad8)") (class "Default")
      (node (ref "JP4") (pin "8") (pinfunction "8_8") (pintype "passive"))
    )
    (net (code "119") (name "unconnected-(JP4-Pad9)") (class "Default")
      (node (ref "JP4") (pin "9") (pinfunction "9_9") (pintype "passive"))
    )
    (net (code "120") (name "unconnected-(JP4-Pad10)") (class "Default")
      (node (ref "JP4") (pin "10") (pinfunction "10_10") (pintype "passive"))
    )
    (net (code "121") (name "unconnected-(JP4-Pad11)") (class "Default")
      (node (ref "JP4") (pin "11") (pinfunction "11_11") (pintype "passive"))
    )
    (net (code "122") (name "unconnected-(JP4-Pad12)") (class "Default")
      (node (ref "JP4") (pin "12") (pinfunction "12_12") (pintype "passive"))
    )
    (net (code "123") (name "unconnected-(JP4-Pad13)") (class "Default")
      (node (ref "JP4") (pin "13") (pinfunction "13_13") (pintype "passive"))
    )
    (net (code "124") (name "unconnected-(JP4-Pad14)") (class "Default")
      (node (ref "JP4") (pin "14") (pinfunction "14_14") (pintype "passive"))
    )
    (net (code "125") (name "unconnected-(JP4-Pad15)") (class "Default")
      (node (ref "JP4") (pin "15") (pinfunction "15_15") (pintype "passive"))
    )
    (net (code "126") (name "unconnected-(JP4-Pad16)") (class "Default")
      (node (ref "JP4") (pin "16") (pinfunction "16_16") (pintype "passive"))
    )
    (net (code "127") (name "unconnected-(JP5-Pad1)") (class "Default")
      (node (ref "JP5") (pin "1") (pinfunction "1_1") (pintype "passive"))
    )
    (net (code "128") (name "unconnected-(JP5-Pad2)") (class "Default")
      (node (ref "JP5") (pin "2") (pinfunction "2_2") (pintype "passive"))
    )
    (net (code "129") (name "unconnected-(JP5-Pad3)") (class "Default")
      (node (ref "JP5") (pin "3") (pinfunction "3_3") (pintype "passive"))
    )
    (net (code "130") (name "unconnected-(JP5-Pad4)") (class "Default")
      (node (ref "JP5") (pin "4") (pinfunction "4_4") (pintype "passive"))
    )
    (net (code "131") (name "unconnected-(JP5-Pad5)") (class "Default")
      (node (ref "JP5") (pin "5") (pinfunction "5_5") (pintype "passive"))
    )
    (net (code "132") (name "unconnected-(JP5-Pad6)") (class "Default")
      (node (ref "JP5") (pin "6") (pinfunction "6_6") (pintype "passive"))
    )
    (net (code "133") (name "unconnected-(JP5-Pad7)") (class "Default")
      (node (ref "JP5") (pin "7") (pinfunction "7_7") (pintype "passive"))
    )
    (net (code "134") (name "unconnected-(JP5-Pad8)") (class "Default")
      (node (ref "JP5") (pin "8") (pinfunction "8_8") (pintype "passive"))
    )
    (net (code "135") (name "unconnected-(JP5-Pad9)") (class "Default")
      (node (ref "JP5") (pin "9") (pinfunction "9_9") (pintype "passive"))
    )
    (net (code "136") (name "unconnected-(JP5-Pad10)") (class "Default")
      (node (ref "JP5") (pin "10") (pinfunction "10_10") (pintype "passive"))
    )
    (net (code "137") (name "unconnected-(JP5-Pad11)") (class "Default")
      (node (ref "JP5") (pin "11") (pinfunction "11_11") (pintype "passive"))
    )
    (net (code "138") (name "unconnected-(JP5-Pad12)") (class "Default")
      (node (ref "JP5") (pin "12") (pinfunction "12_12") (pintype "passive"))
    )
    (net (code "139") (name "unconnected-(JP5-Pad13)") (class "Default")
      (node (ref "JP5") (pin "13") (pinfunction "13_13") (pintype "passive"))
    )
    (net (code "140") (name "unconnected-(JP5-Pad14)") (class "Default")
      (node (ref "JP5") (pin "14") (pinfunction "14_14") (pintype "passive"))
    )
    (net (code "141") (name "unconnected-(JP5-Pad15)") (class "Default")
      (node (ref "JP5") (pin "15") (pinfunction "15_15") (pintype "passive"))
    )
    (net (code "142") (name "unconnected-(JP5-Pad16)") (class "Default")
      (node (ref "JP5") (pin "16") (pinfunction "16_16") (pintype "passive"))
    )
    (net (code "143") (name "unconnected-(JP6-Pad1)") (class "Default")
      (node (ref "JP6") (pin "1") (pinfunction "1_1") (pintype "passive"))
    )
    (net (code "144") (name "unconnected-(JP6-Pad2)") (class "Default")
      (node (ref "JP6") (pin "2") (pinfunction "2_2") (pintype "passive"))
    )
    (net (code "145") (name "unconnected-(JP6-Pad3)") (class "Default")
      (node (ref "JP6") (pin "3") (pinfunction "3_3") (pintype "passive"))
    )
    (net (code "146") (name "unconnected-(JP6-Pad4)") (class "Default")
      (node (ref "JP6") (pin "4") (pinfunction "4_4") (pintype "passive"))
    )
    (net (code "147") (name "unconnected-(JP6-Pad5)") (class "Default")
      (node (ref "JP6") (pin "5") (pinfunction "5_5") (pintype "passive"))
    )
    (net (code "148") (name "unconnected-(JP6-Pad6)") (class "Default")
      (node (ref "JP6") (pin "6") (pinfunction "6_6") (pintype "passive"))
    )
    (net (code "149") (name "unconnected-(JP6-Pad7)") (class "Default")
      (node (ref "JP6") (pin "7") (pinfunction "7_7") (pintype "passive"))
    )
    (net (code "150") (name "unconnected-(JP6-Pad8)") (class "Default")
      (node (ref "JP6") (pin "8") (pinfunction "8_8") (pintype "passive"))
    )
    (net (code "151") (name "unconnected-(JP6-Pad9)") (class "Default")
      (node (ref "JP6") (pin "9") (pinfunction "9_9") (pintype "passive"))
    )
    (net (code "152") (name "unconnected-(JP6-Pad10)") (class "Default")
      (node (ref "JP6") (pin "10") (pinfunction "10_10") (pintype "passive"))
    )
    (net (code "153") (name "unconnected-(JP6-Pad11)") (class "Default")
      (node (ref "JP6") (pin "11") (pinfunction "11_11") (pintype "passive"))
    )
    (net (code "154") (name "unconnected-(JP6-Pad12)") (class "Default")
      (node (ref "JP6") (pin "12") (pinfunction "12_12") (pintype "passive"))
    )
    (net (code "155") (name "unconnected-(JP6-Pad13)") (class "Default")
      (node (ref "JP6") (pin "13") (pinfunction "13_13") (pintype "passive"))
    )
    (net (code "156") (name "unconnected-(JP6-Pad14)") (class "Default")
      (node (ref "JP6") (pin "14") (pinfunction "14_14") (pintype "passive"))
    )
    (net (code "157") (name "unconnected-(JP6-Pad15)") (class "Default")
      (node (ref "JP6") (pin "15") (pinfunction "15_15") (pintype "passive"))
    )
    (net (code "158") (name "unconnected-(JP6-Pad16)") (class "Default")
      (node (ref "JP6") (pin "16") (pinfunction "16_16") (pintype "passive"))
    )
    (net (code "159") (name "unconnected-(JP8-Pad1)") (class "Default")
      (node (ref "JP8") (pin "1") (pinfunction "1_1") (pintype "passive"))
    )
    (net (code "160") (name "unconnected-(JP8-Pad2)") (class "Default")
      (node (ref "JP8") (pin "2") (pinfunction "2_2") (pintype "passive"))
    )
    (net (code "161") (name "unconnected-(JP8-Pad3)") (class "Default")
      (node (ref "JP8") (pin "3") (pinfunction "3_3") (pintype "passive"))
    )
    (net (code "162") (name "unconnected-(JP8-Pad4)") (class "Default")
      (node (ref "JP8") (pin "4") (pinfunction "4_4") (pintype "passive"))
    )
    (net (code "163") (name "unconnected-(JP8-Pad5)") (class "Default")
      (node (ref "JP8") (pin "5") (pinfunction "5_5") (pintype "passive"))
    )
    (net (code "164") (name "unconnected-(JP8-Pad6)") (class "Default")
      (node (ref "JP8") (pin "6") (pinfunction "6_6") (pintype "passive"))
    )
    (net (code "165") (name "unconnected-(JP8-Pad7)") (class "Default")
      (node (ref "JP8") (pin "7") (pinfunction "7_7") (pintype "passive"))
    )
    (net (code "166") (name "unconnected-(JP8-Pad8)") (class "Default")
      (node (ref "JP8") (pin "8") (pinfunction "8_8") (pintype "passive"))
    )
    (net (code "167") (name "unconnected-(JP8-Pad9)") (class "Default")
      (node (ref "JP8") (pin "9") (pinfunction "9_9") (pintype "passive"))
    )
    (net (code "168") (name "unconnected-(JP8-Pad10)") (class "Default")
      (node (ref "JP8") (pin "10") (pinfunction "10_10") (pintype "passive"))
    )
    (net (code "169") (name "unconnected-(JP8-Pad11)") (class "Default")
      (node (ref "JP8") (pin "11") (pinfunction "11_11") (pintype "passive"))
    )
    (net (code "170") (name "unconnected-(JP8-Pad12)") (class "Default")
      (node (ref "JP8") (pin "12") (pinfunction "12_12") (pintype "passive"))
    )
    (net (code "171") (name "unconnected-(JP8-Pad13)") (class "Default")
      (node (ref "JP8") (pin "13") (pinfunction "13_13") (pintype "passive"))
    )
    (net (code "172") (name "unconnected-(JP8-Pad14)") (class "Default")
      (node (ref "JP8") (pin "14") (pinfunction "14_14") (pintype "passive"))
    )
    (net (code "173") (name "unconnected-(JP8-Pad15)") (class "Default")
      (node (ref "JP8") (pin "15") (pinfunction "15_15") (pintype "passive"))
    )
    (net (code "174") (name "unconnected-(JP8-Pad16)") (class "Default")
      (node (ref "JP8") (pin "16") (pinfunction "16_16") (pintype "passive"))
    )
  )
)
